# DHT22_Humidity-Temp.net
KiCad netlist of a schematic drawn in EAGLE
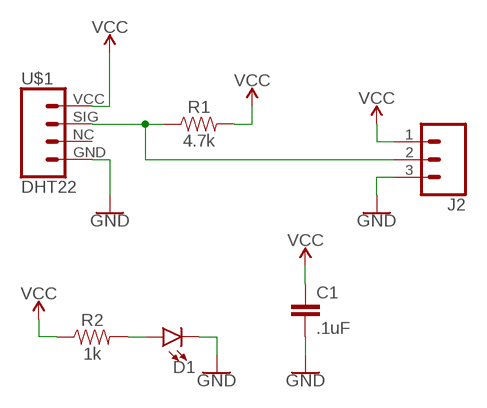
[diagram p0: schematic, sheet 1]

(export (version "E")
  (design (tool "Eeschema 10.0.6"))
  (components
    (comp (ref "C1")
      (value ".1uF")
      (footprint "eagle-import:0805")
      (libsource (lib "eagle-import") (part "1.0UF-0805-25V-(+80/-20%)"))
    )
    (comp (ref "D1")
      (value "LED-3MM-NO_SILK")
      (footprint "eagle-import:LED_3MM-NS")
      (libsource (lib "eagle-import") (part "LED-3MM-NO_SILK"))
    )
    (comp (ref "J2")
      (value "CONN_03LONGPADS")
      (footprint "eagle-import:1X03_LONGPADS")
      (libsource (lib "eagle-import") (part "CONN_03LONGPADS"))
    )
    (comp (ref "R1")
      (value "4.7k")
      (footprint "eagle-import:0805")
      (libsource (lib "eagle-import") (part "0.3OHM-0805-1/8W-1%"))
    )
    (comp (ref "R2")
      (value "1k")
      (footprint "eagle-import:0805")
      (libsource (lib "eagle-import") (part "0.3OHM-0805-1/8W-1%"))
    )
    (comp (ref "U$1")
      (value "DHT22")
      (footprint "eagle-import:DHT22")
      (libsource (lib "eagle-import") (part "DHT22"))
    )
  )
  (nets
    (net (code "1") (name "GND") (class "Default")
      (node (ref "C1") (pin "2") (pinfunction "2_2") (pintype "passive"))
      (node (ref "D1") (pin "K") (pinfunction "C_K") (pintype "passive"))
      (node (ref "J2") (pin "3") (pinfunction "3_3") (pintype "passive"))
      (node (ref "U$1") (pin "GND") (pinfunction "1_GND") (pintype "passive"))
    )
    (net (code "2") (name "Net-(D1-PadA)") (class "Default")
      (node (ref "D1") (pin "A") (pinfunction "A_A") (pintype "passive"))
      (node (ref "R2") (pin "2") (pinfunction "2_2") (pintype "passive"))
    )
    (net (code "3") (name "Net-(U$1-3)") (class "Default")
      (node (ref "J2") (pin "2") (pinfunction "2_2") (pintype "passive"))
      (node (ref "R1") (pin "1") (pinfunction "1_1") (pintype "passive"))
      (node (ref "U$1") (pin "SIG") (pinfunction "3_SIG") (pintype "passive"))
    )
    (net (code "4") (name "VCC") (class "Default")
      (node (ref "C1") (pin "1") (pinfunction "1_1") (pintype "passive"))
      (node (ref "J2") (pin "1") (pinfunction "1_1") (pintype "passive"))
      (node (ref "R1") (pin "2") (pinfunction "2_2") (pintype "passive"))
      (node (ref "R2") (pin "1") (pinfunction "1_1") (pintype "passive"))
      (node (ref "U$1") (pin "VCC") (pinfunction "4_VCC") (pintype "passive"))
    )
    (net (code "5") (name "unconnected-(U$1-2-PadNC)") (class "Default")
      (node (ref "U$1") (pin "NC") (pinfunction "2_NC") (pintype "passive"))
    )
  )
)
